# SCH_Dashboy_camera_2023-03-13.net
KiCad netlist of a schematic drawn in EasyEDA
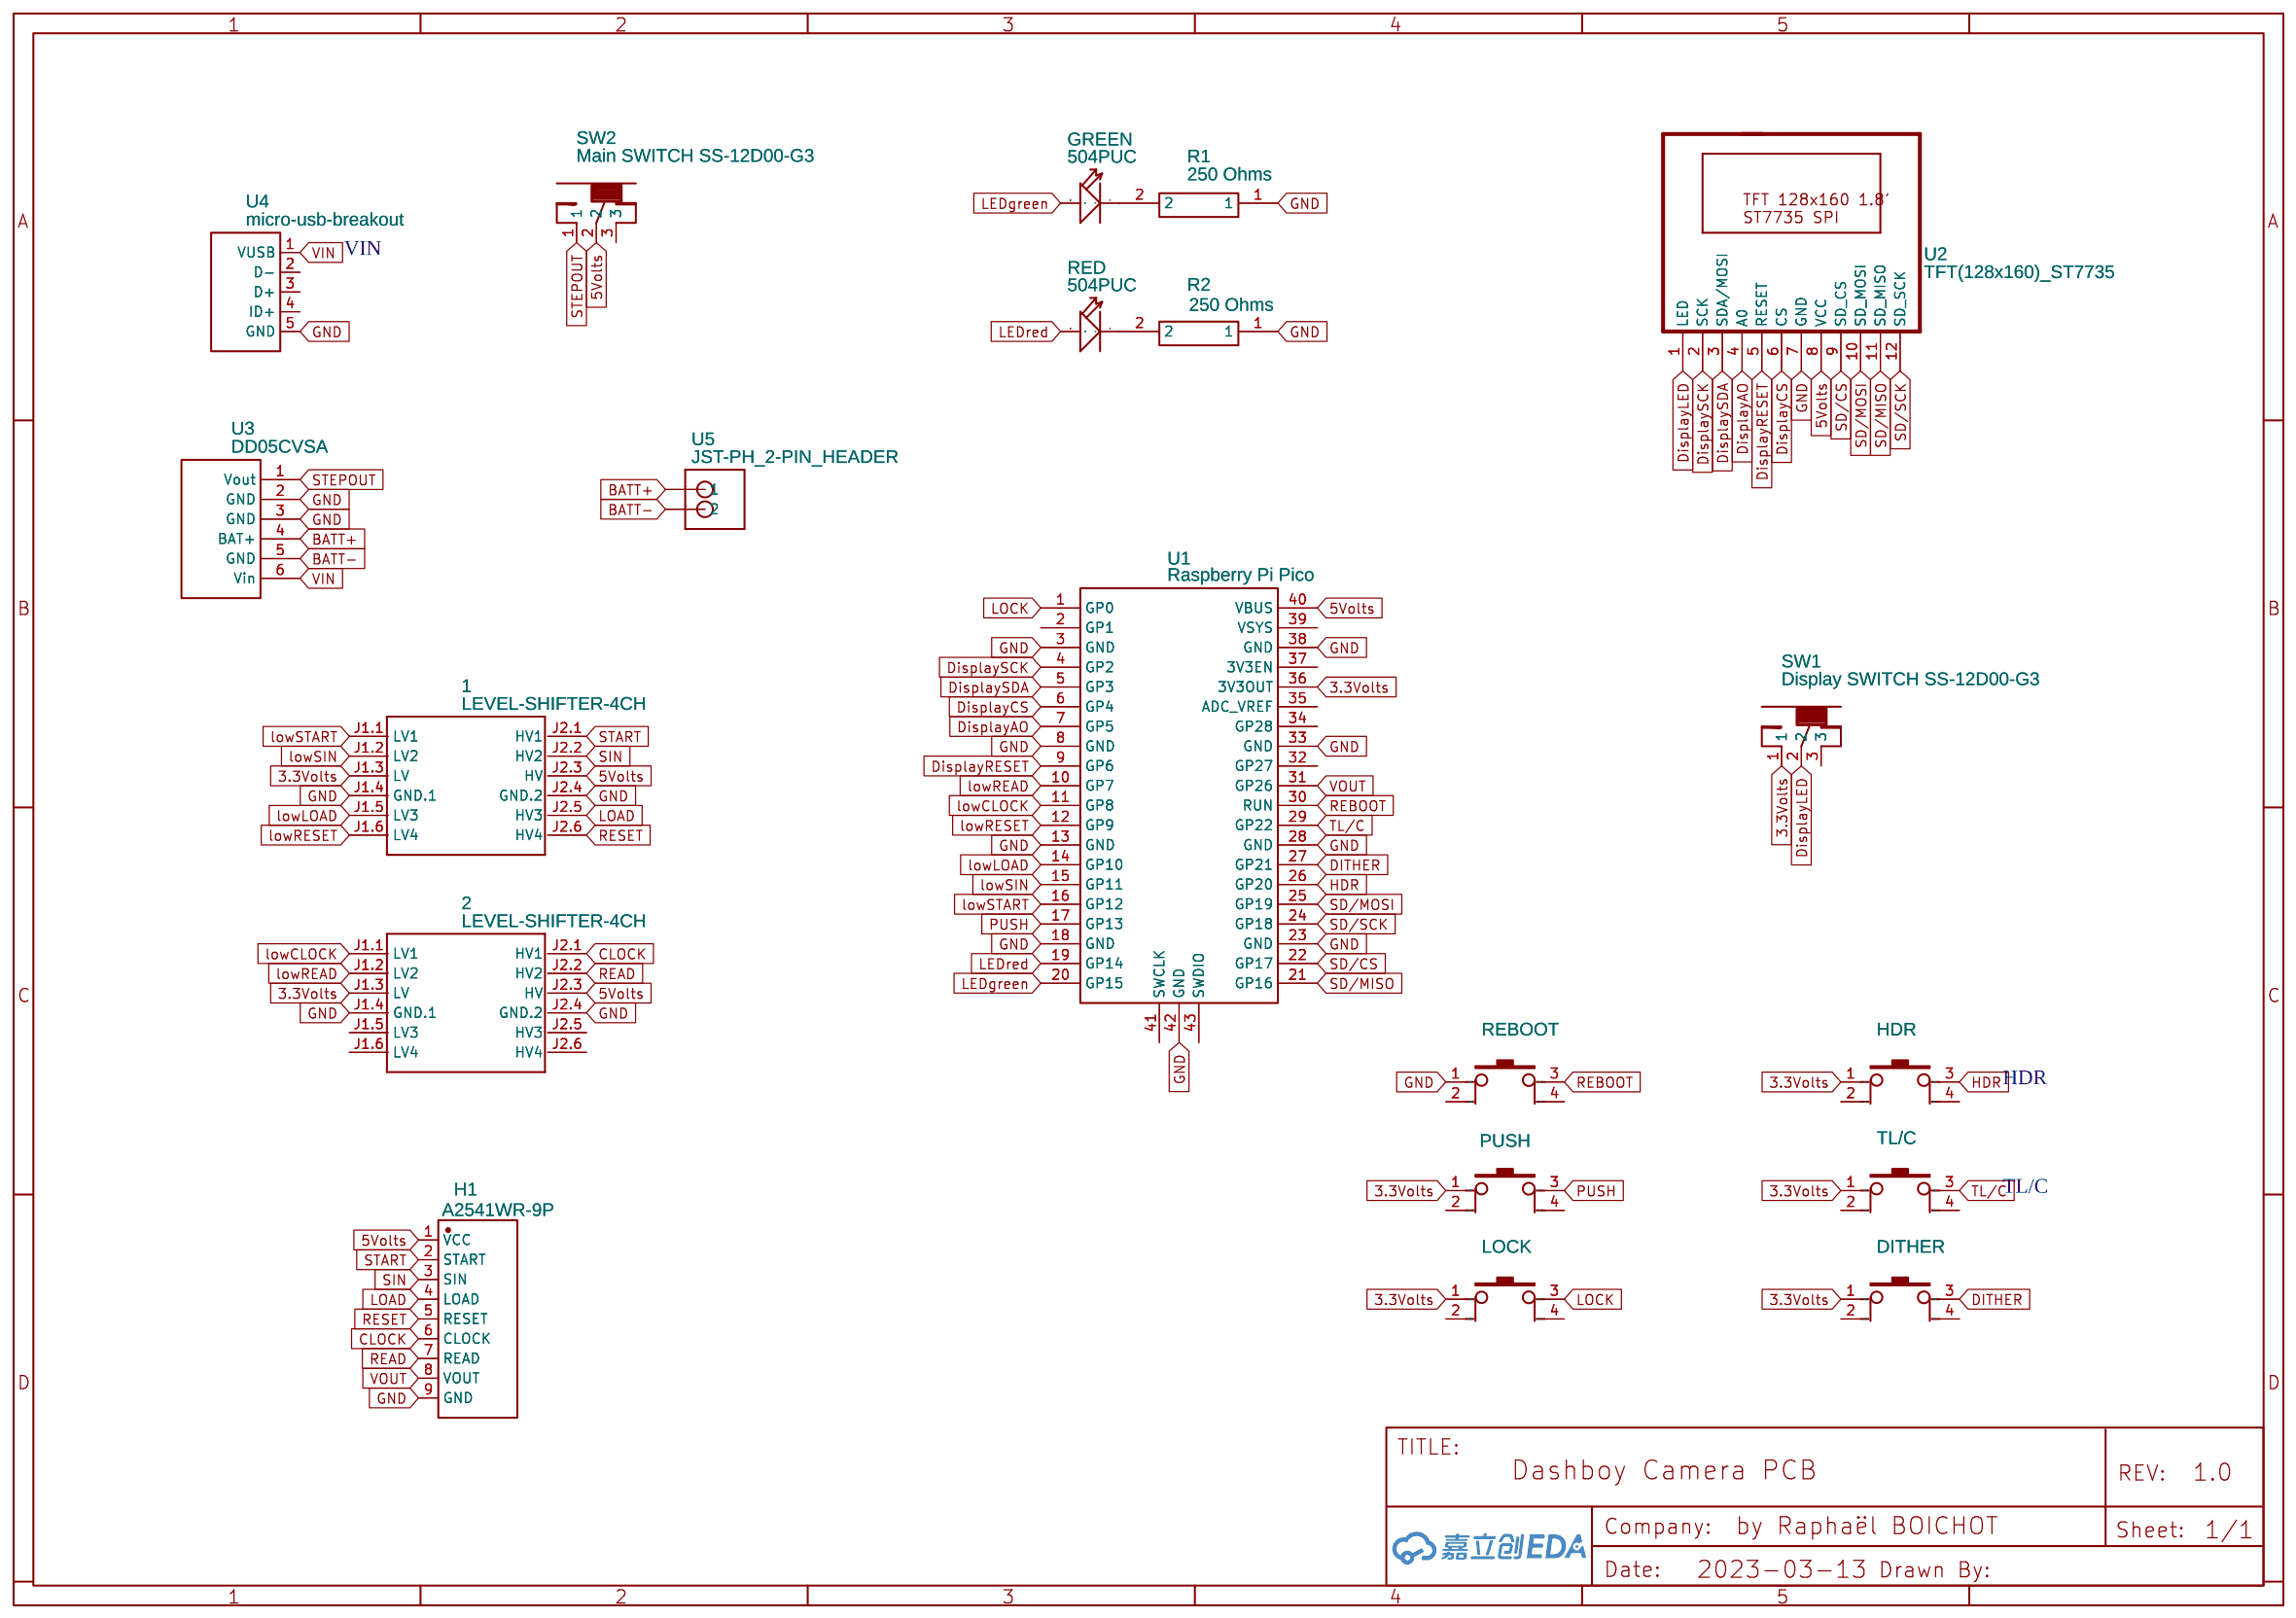
[diagram p0: schematic sheet]

(export (version "E")
  (design (tool "Eeschema 10.0.6"))
  (components
    (comp (ref "1") (value "LEVEL-SHIFTER-4CH") (libsource (lib "") (part "LEVEL-SHIFTER-4CH")))
    (comp (ref "2") (value "LEVEL-SHIFTER-4CH") (libsource (lib "") (part "LEVEL-SHIFTER-4CH")))
    (comp (ref "DITHER")
      (value "BoutonPoussoir")
      (fields
        (field (name "BOM_Manufacturer Part") "button6*6*8")
        (field (name "BOM_Supplier Part") "C59982")
      )
      (libsource (lib "") (part "BoutonPoussoir_1"))
    )
    (comp (ref "GREEN") (value "504PUC") (libsource (lib "") (part "504PUC_1")))
    (comp (ref "H1")
      (value "A2541WR-9P")
      (fields (field (name "BOM_Supplier Part") "C225495"))
      (libsource (lib "") (part "A2541WR-9P"))
    )
    (comp (ref "HDR")
      (value "BoutonPoussoir")
      (fields
        (field (name "BOM_Manufacturer Part") "button6*6*8")
        (field (name "BOM_Supplier Part") "C59982")
      )
      (libsource (lib "") (part "BoutonPoussoir_2"))
    )
    (comp (ref "LOCK")
      (value "BoutonPoussoir")
      (fields
        (field (name "BOM_Manufacturer Part") "button6*6*8")
        (field (name "BOM_Supplier Part") "C59982")
      )
      (libsource (lib "") (part "BoutonPoussoir"))
    )
    (comp (ref "PUSH")
      (value "BoutonPoussoir")
      (fields
        (field (name "BOM_Manufacturer Part") "button6*6*8")
        (field (name "BOM_Supplier Part") "C59982")
      )
      (libsource (lib "") (part "BoutonPoussoir_3"))
    )
    (comp (ref "R1") (value "250 Ohms") (libsource (lib "") (part "RESITOR")))
    (comp (ref "R2") (value "250 Ohms") (libsource (lib "") (part "RESITOR")))
    (comp (ref "REBOOT")
      (value "BoutonPoussoir")
      (fields
        (field (name "BOM_Manufacturer Part") "button6*6*8")
        (field (name "BOM_Supplier Part") "C59982")
      )
      (libsource (lib "") (part "BoutonPoussoir_4"))
    )
    (comp (ref "RED") (value "504PUC") (libsource (lib "") (part "504PUC")))
    (comp (ref "SW1")
      (value "Display SWITCH SS-12D00-G3")
      (fields (field (name "BOM_Manufacturer Part") "TOGGLE SWITCH SS-12D00-G3"))
      (libsource (lib "") (part "TOGGLE SWITCH SS-12D00-G3_1"))
    )
    (comp (ref "SW2")
      (value "Main SWITCH SS-12D00-G3")
      (fields (field (name "BOM_Manufacturer Part") "TOGGLE SWITCH SS-12D00-G3"))
      (libsource (lib "") (part "TOGGLE SWITCH SS-12D00-G3"))
    )
    (comp (ref "TL/C")
      (value "BoutonPoussoir")
      (fields
        (field (name "BOM_Manufacturer Part") "button6*6*8")
        (field (name "BOM_Supplier Part") "C59982")
      )
      (libsource (lib "") (part "BoutonPoussoir_5"))
    )
    (comp (ref "U1") (value "Raspberry Pi Pico") (libsource (lib "") (part "Raspberry Pi Pico")))
    (comp (ref "U2") (value "TFT(128x160)_ST7735") (libsource (lib "") (part "TFT(128x160)_ST7735")))
    (comp (ref "U3") (value "DD05CVSA") (libsource (lib "") (part "DD05CVSA")))
    (comp (ref "U4") (value "micro-usb-breakout") (libsource (lib "") (part "micro-usb-breakout")))
    (comp (ref "U5") (value "JST-PH_2-PIN_HEADER") (libsource (lib "") (part "JST-PH_2-PIN_HEADER")))
  )
  (nets
    (net (code "1") (name "3.3Volts") (class "Default")
      (node (ref "1") (pin "J1.3") (pinfunction "LV_J1.3") (pintype "bidirectional"))
      (node (ref "2") (pin "J1.3") (pinfunction "LV_J1.3") (pintype "bidirectional"))
      (node (ref "DITHER") (pin "1") (pinfunction "1_1") (pintype "input"))
      (node (ref "HDR") (pin "1") (pinfunction "1_1") (pintype "input"))
      (node (ref "LOCK") (pin "1") (pinfunction "1_1") (pintype "input"))
      (node (ref "PUSH") (pin "1") (pinfunction "1_1") (pintype "input"))
      (node (ref "SW1") (pin "1") (pinfunction "1_1") (pintype "bidirectional"))
      (node (ref "TL/C") (pin "1") (pinfunction "1_1") (pintype "input"))
      (node (ref "U1") (pin "36") (pinfunction "3V3OUT_36") (pintype "unspecified"))
    )
    (net (code "2") (name "5Volts") (class "Default")
      (node (ref "1") (pin "J2.3") (pinfunction "HV_J2.3") (pintype "bidirectional"))
      (node (ref "2") (pin "J2.3") (pinfunction "HV_J2.3") (pintype "bidirectional"))
      (node (ref "H1") (pin "1") (pinfunction "VCC_1") (pintype "unspecified"))
      (node (ref "SW2") (pin "2") (pinfunction "2_2") (pintype "bidirectional"))
      (node (ref "U1") (pin "40") (pinfunction "VBUS_40") (pintype "unspecified"))
      (node (ref "U2") (pin "8") (pinfunction "VCC_8") (pintype "input"))
    )
    (net (code "3") (name "BATT+") (class "Default")
      (node (ref "U3") (pin "4") (pinfunction "BAT+_4") (pintype "unspecified"))
      (node (ref "U5") (pin "P1") (pinfunction "1_P1") (pintype "unspecified"))
    )
    (net (code "4") (name "BATT-") (class "Default")
      (node (ref "U3") (pin "5") (pinfunction "GND_5") (pintype "unspecified"))
      (node (ref "U5") (pin "P2") (pinfunction "2_P2") (pintype "unspecified"))
    )
    (net (code "5") (name "CLOCK") (class "Default")
      (node (ref "2") (pin "J2.1") (pinfunction "HV1_J2.1") (pintype "bidirectional"))
      (node (ref "H1") (pin "6") (pinfunction "CLOCK_6") (pintype "unspecified"))
    )
    (net (code "6") (name "DITHER") (class "Default")
      (node (ref "DITHER") (pin "3") (pinfunction "3_3") (pintype "input"))
      (node (ref "U1") (pin "27") (pinfunction "GP21_27") (pintype "unspecified"))
    )
    (net (code "7") (name "DisplayAO") (class "Default")
      (node (ref "U1") (pin "7") (pinfunction "GP5_7") (pintype "unspecified"))
      (node (ref "U2") (pin "4") (pinfunction "A0_4") (pintype "input"))
    )
    (net (code "8") (name "DisplayCS") (class "Default")
      (node (ref "U1") (pin "6") (pinfunction "GP4_6") (pintype "unspecified"))
      (node (ref "U2") (pin "6") (pinfunction "CS_6") (pintype "input"))
    )
    (net (code "9") (name "DisplayLED") (class "Default")
      (node (ref "SW1") (pin "2") (pinfunction "2_2") (pintype "bidirectional"))
      (node (ref "U2") (pin "1") (pinfunction "LED_1") (pintype "passive"))
    )
    (net (code "10") (name "DisplayRESET") (class "Default")
      (node (ref "U1") (pin "9") (pinfunction "GP6_9") (pintype "unspecified"))
      (node (ref "U2") (pin "5") (pinfunction "RESET_5") (pintype "input"))
    )
    (net (code "11") (name "DisplaySCK") (class "Default")
      (node (ref "U1") (pin "4") (pinfunction "GP2_4") (pintype "unspecified"))
      (node (ref "U2") (pin "2") (pinfunction "SCK_2") (pintype "output"))
    )
    (net (code "12") (name "DisplaySDA") (class "Default")
      (node (ref "U1") (pin "5") (pinfunction "GP3_5") (pintype "unspecified"))
      (node (ref "U2") (pin "3") (pinfunction "SDA/MOSI_3") (pintype "input"))
    )
    (net (code "13") (name "GND") (class "Default")
      (node (ref "1") (pin "J1.4") (pinfunction "GND.1_J1.4") (pintype "bidirectional"))
      (node (ref "1") (pin "J2.4") (pinfunction "GND.2_J2.4") (pintype "bidirectional"))
      (node (ref "2") (pin "J1.4") (pinfunction "GND.1_J1.4") (pintype "bidirectional"))
      (node (ref "2") (pin "J2.4") (pinfunction "GND.2_J2.4") (pintype "bidirectional"))
      (node (ref "H1") (pin "9") (pinfunction "GND_9") (pintype "unspecified"))
      (node (ref "R1") (pin "1") (pinfunction "1_1") (pintype "unspecified"))
      (node (ref "R2") (pin "1") (pinfunction "1_1") (pintype "unspecified"))
      (node (ref "REBOOT") (pin "1") (pinfunction "1_1") (pintype "input"))
      (node (ref "U1") (pin "13") (pinfunction "GND_13") (pintype "unspecified"))
      (node (ref "U1") (pin "18") (pinfunction "GND_18") (pintype "unspecified"))
      (node (ref "U1") (pin "23") (pinfunction "GND_23") (pintype "unspecified"))
      (node (ref "U1") (pin "28") (pinfunction "GND_28") (pintype "unspecified"))
      (node (ref "U1") (pin "3") (pinfunction "GND_3") (pintype "unspecified"))
      (node (ref "U1") (pin "33") (pinfunction "GND_33") (pintype "unspecified"))
      (node (ref "U1") (pin "38") (pinfunction "GND_38") (pintype "unspecified"))
      (node (ref "U1") (pin "42") (pinfunction "GND_42") (pintype "unspecified"))
      (node (ref "U1") (pin "8") (pinfunction "GND_8") (pintype "unspecified"))
      (node (ref "U2") (pin "7") (pinfunction "GND_7") (pintype "unspecified"))
      (node (ref "U3") (pin "2") (pinfunction "GND_2") (pintype "unspecified"))
      (node (ref "U3") (pin "3") (pinfunction "GND_3") (pintype "unspecified"))
      (node (ref "U4") (pin "5") (pinfunction "GND_5") (pintype "unspecified"))
    )
    (net (code "14") (name "HDR") (class "Default")
      (node (ref "HDR") (pin "3") (pinfunction "3_3") (pintype "input"))
      (node (ref "U1") (pin "26") (pinfunction "GP20_26") (pintype "unspecified"))
    )
    (net (code "15") (name "LEDgreen") (class "Default")
      (node (ref "GREEN") (pin "+") (pinfunction "+_+") (pintype "unspecified"))
      (node (ref "U1") (pin "20") (pinfunction "GP15_20") (pintype "unspecified"))
    )
    (net (code "16") (name "LEDred") (class "Default")
      (node (ref "RED") (pin "+") (pinfunction "+_+") (pintype "unspecified"))
      (node (ref "U1") (pin "19") (pinfunction "GP14_19") (pintype "unspecified"))
    )
    (net (code "17") (name "LOAD") (class "Default")
      (node (ref "1") (pin "J2.5") (pinfunction "HV3_J2.5") (pintype "bidirectional"))
      (node (ref "H1") (pin "4") (pinfunction "LOAD_4") (pintype "unspecified"))
    )
    (net (code "18") (name "LOCK") (class "Default")
      (node (ref "LOCK") (pin "3") (pinfunction "3_3") (pintype "input"))
      (node (ref "U1") (pin "1") (pinfunction "GP0_1") (pintype "unspecified"))
    )
    (net (code "19") (name "Net-(GREEN-Pad-)") (class "Default")
      (node (ref "GREEN") (pin "-") (pinfunction "-_-") (pintype "unspecified"))
      (node (ref "R1") (pin "2") (pinfunction "2_2") (pintype "unspecified"))
    )
    (net (code "20") (name "Net-(R2-Pad2)") (class "Default")
      (node (ref "R2") (pin "2") (pinfunction "2_2") (pintype "unspecified"))
      (node (ref "RED") (pin "-") (pinfunction "-_-") (pintype "unspecified"))
    )
    (net (code "21") (name "PUSH") (class "Default")
      (node (ref "PUSH") (pin "3") (pinfunction "3_3") (pintype "input"))
      (node (ref "U1") (pin "17") (pinfunction "GP13_17") (pintype "unspecified"))
    )
    (net (code "22") (name "READ") (class "Default")
      (node (ref "2") (pin "J2.2") (pinfunction "HV2_J2.2") (pintype "bidirectional"))
      (node (ref "H1") (pin "7") (pinfunction "READ_7") (pintype "unspecified"))
    )
    (net (code "23") (name "REBOOT") (class "Default")
      (node (ref "REBOOT") (pin "3") (pinfunction "3_3") (pintype "input"))
      (node (ref "U1") (pin "30") (pinfunction "RUN_30") (pintype "unspecified"))
    )
    (net (code "24") (name "RESET") (class "Default")
      (node (ref "1") (pin "J2.6") (pinfunction "HV4_J2.6") (pintype "bidirectional"))
      (node (ref "H1") (pin "5") (pinfunction "RESET_5") (pintype "unspecified"))
    )
    (net (code "25") (name "SD{slash}CS") (class "Default")
      (node (ref "U1") (pin "22") (pinfunction "GP17_22") (pintype "unspecified"))
      (node (ref "U2") (pin "9") (pinfunction "SD_CS_9") (pintype "input"))
    )
    (net (code "26") (name "SD{slash}MISO") (class "Default")
      (node (ref "U1") (pin "21") (pinfunction "GP16_21") (pintype "unspecified"))
      (node (ref "U2") (pin "11") (pinfunction "SD_MISO_11") (pintype "input"))
    )
    (net (code "27") (name "SD{slash}MOSI") (class "Default")
      (node (ref "U1") (pin "25") (pinfunction "GP19_25") (pintype "unspecified"))
      (node (ref "U2") (pin "10") (pinfunction "SD_MOSI_10") (pintype "input"))
    )
    (net (code "28") (name "SD{slash}SCK") (class "Default")
      (node (ref "U1") (pin "24") (pinfunction "GP18_24") (pintype "unspecified"))
      (node (ref "U2") (pin "12") (pinfunction "SD_SCK_12") (pintype "input"))
    )
    (net (code "29") (name "SIN") (class "Default")
      (node (ref "1") (pin "J2.2") (pinfunction "HV2_J2.2") (pintype "bidirectional"))
      (node (ref "H1") (pin "3") (pinfunction "SIN_3") (pintype "unspecified"))
    )
    (net (code "30") (name "START") (class "Default")
      (node (ref "1") (pin "J2.1") (pinfunction "HV1_J2.1") (pintype "bidirectional"))
      (node (ref "H1") (pin "2") (pinfunction "START_2") (pintype "unspecified"))
    )
    (net (code "31") (name "STEPOUT") (class "Default")
      (node (ref "SW2") (pin "1") (pinfunction "1_1") (pintype "bidirectional"))
      (node (ref "U3") (pin "1") (pinfunction "Vout_1") (pintype "unspecified"))
    )
    (net (code "32") (name "TL{slash}C") (class "Default")
      (node (ref "TL/C") (pin "3") (pinfunction "3_3") (pintype "input"))
      (node (ref "U1") (pin "29") (pinfunction "GP22_29") (pintype "unspecified"))
    )
    (net (code "33") (name "VIN") (class "Default")
      (node (ref "U3") (pin "6") (pinfunction "Vin_6") (pintype "unspecified"))
      (node (ref "U4") (pin "1") (pinfunction "VUSB_1") (pintype "unspecified"))
    )
    (net (code "34") (name "VOUT") (class "Default")
      (node (ref "H1") (pin "8") (pinfunction "VOUT_8") (pintype "unspecified"))
      (node (ref "U1") (pin "31") (pinfunction "GP26_31") (pintype "unspecified"))
    )
    (net (code "35") (name "lowCLOCK") (class "Default")
      (node (ref "2") (pin "J1.1") (pinfunction "LV1_J1.1") (pintype "bidirectional"))
      (node (ref "U1") (pin "11") (pinfunction "GP8_11") (pintype "unspecified"))
    )
    (net (code "36") (name "lowLOAD") (class "Default")
      (node (ref "1") (pin "J1.5") (pinfunction "LV3_J1.5") (pintype "bidirectional"))
      (node (ref "U1") (pin "14") (pinfunction "GP10_14") (pintype "unspecified"))
    )
    (net (code "37") (name "lowREAD") (class "Default")
      (node (ref "2") (pin "J1.2") (pinfunction "LV2_J1.2") (pintype "bidirectional"))
      (node (ref "U1") (pin "10") (pinfunction "GP7_10") (pintype "unspecified"))
    )
    (net (code "38") (name "lowRESET") (class "Default")
      (node (ref "1") (pin "J1.6") (pinfunction "LV4_J1.6") (pintype "bidirectional"))
      (node (ref "U1") (pin "12") (pinfunction "GP9_12") (pintype "unspecified"))
    )
    (net (code "39") (name "lowSIN") (class "Default")
      (node (ref "1") (pin "J1.2") (pinfunction "LV2_J1.2") (pintype "bidirectional"))
      (node (ref "U1") (pin "15") (pinfunction "GP11_15") (pintype "unspecified"))
    )
    (net (code "40") (name "lowSTART") (class "Default")
      (node (ref "1") (pin "J1.1") (pinfunction "LV1_J1.1") (pintype "bidirectional"))
      (node (ref "U1") (pin "16") (pinfunction "GP12_16") (pintype "unspecified"))
    )
    (net (code "41") (name "unconnected-(2-HV3-PadJ2.5)") (class "Default")
      (node (ref "2") (pin "J2.5") (pinfunction "HV3_J2.5") (pintype "bidirectional"))
    )
    (net (code "42") (name "unconnected-(2-HV4-PadJ2.6)") (class "Default")
      (node (ref "2") (pin "J2.6") (pinfunction "HV4_J2.6") (pintype "bidirectional"))
    )
    (net (code "43") (name "unconnected-(2-LV3-PadJ1.5)") (class "Default")
      (node (ref "2") (pin "J1.5") (pinfunction "LV3_J1.5") (pintype "bidirectional"))
    )
    (net (code "44") (name "unconnected-(2-LV4-PadJ1.6)") (class "Default")
      (node (ref "2") (pin "J1.6") (pinfunction "LV4_J1.6") (pintype "bidirectional"))
    )
    (net (code "45") (name "unconnected-(DITHER-Pad2)") (class "Default")
      (node (ref "DITHER") (pin "2") (pinfunction "2_2") (pintype "input"))
    )
    (net (code "46") (name "unconnected-(DITHER-Pad4)") (class "Default")
      (node (ref "DITHER") (pin "4") (pinfunction "4_4") (pintype "input"))
    )
    (net (code "47") (name "unconnected-(HDR-Pad2)") (class "Default")
      (node (ref "HDR") (pin "2") (pinfunction "2_2") (pintype "input"))
    )
    (net (code "48") (name "unconnected-(HDR-Pad4)") (class "Default")
      (node (ref "HDR") (pin "4") (pinfunction "4_4") (pintype "input"))
    )
    (net (code "49") (name "unconnected-(LOCK-Pad2)") (class "Default")
      (node (ref "LOCK") (pin "2") (pinfunction "2_2") (pintype "input"))
    )
    (net (code "50") (name "unconnected-(LOCK-Pad4)") (class "Default")
      (node (ref "LOCK") (pin "4") (pinfunction "4_4") (pintype "input"))
    )
    (net (code "51") (name "unconnected-(PUSH-Pad2)") (class "Default")
      (node (ref "PUSH") (pin "2") (pinfunction "2_2") (pintype "input"))
    )
    (net (code "52") (name "unconnected-(PUSH-Pad4)") (class "Default")
      (node (ref "PUSH") (pin "4") (pinfunction "4_4") (pintype "input"))
    )
    (net (code "53") (name "unconnected-(REBOOT-Pad2)") (class "Default")
      (node (ref "REBOOT") (pin "2") (pinfunction "2_2") (pintype "input"))
    )
    (net (code "54") (name "unconnected-(REBOOT-Pad4)") (class "Default")
      (node (ref "REBOOT") (pin "4") (pinfunction "4_4") (pintype "input"))
    )
    (net (code "55") (name "unconnected-(SW1-Pad3)") (class "Default")
      (node (ref "SW1") (pin "3") (pinfunction "3_3") (pintype "unspecified"))
    )
    (net (code "56") (name "unconnected-(SW2-Pad3)") (class "Default")
      (node (ref "SW2") (pin "3") (pinfunction "3_3") (pintype "unspecified"))
    )
    (net (code "57") (name "unconnected-(TL/C-Pad2)") (class "Default")
      (node (ref "TL/C") (pin "2") (pinfunction "2_2") (pintype "input"))
    )
    (net (code "58") (name "unconnected-(TL/C-Pad4)") (class "Default")
      (node (ref "TL/C") (pin "4") (pinfunction "4_4") (pintype "input"))
    )
    (net (code "59") (name "unconnected-(U1-3V3EN-Pad37)") (class "Default")
      (node (ref "U1") (pin "37") (pinfunction "3V3EN_37") (pintype "unspecified"))
    )
    (net (code "60") (name "unconnected-(U1-ADC_VREF-Pad35)") (class "Default")
      (node (ref "U1") (pin "35") (pinfunction "ADC_VREF_35") (pintype "unspecified"))
    )
    (net (code "61") (name "unconnected-(U1-GP1-Pad2)") (class "Default")
      (node (ref "U1") (pin "2") (pinfunction "GP1_2") (pintype "unspecified"))
    )
    (net (code "62") (name "unconnected-(U1-GP27-Pad32)") (class "Default")
      (node (ref "U1") (pin "32") (pinfunction "GP27_32") (pintype "unspecified"))
    )
    (net (code "63") (name "unconnected-(U1-GP28-Pad34)") (class "Default")
      (node (ref "U1") (pin "34") (pinfunction "GP28_34") (pintype "unspecified"))
    )
    (net (code "64") (name "unconnected-(U1-SWCLK-Pad41)") (class "Default")
      (node (ref "U1") (pin "41") (pinfunction "SWCLK_41") (pintype "unspecified"))
    )
    (net (code "65") (name "unconnected-(U1-SWDIO-Pad43)") (class "Default")
      (node (ref "U1") (pin "43") (pinfunction "SWDIO_43") (pintype "unspecified"))
    )
    (net (code "66") (name "unconnected-(U1-VSYS-Pad39)") (class "Default")
      (node (ref "U1") (pin "39") (pinfunction "VSYS_39") (pintype "unspecified"))
    )
    (net (code "67") (name "unconnected-(U4-D+-Pad3)") (class "Default")
      (node (ref "U4") (pin "3") (pinfunction "D+_3") (pintype "unspecified"))
    )
    (net (code "68") (name "unconnected-(U4-D--Pad2)") (class "Default")
      (node (ref "U4") (pin "2") (pinfunction "D-_2") (pintype "unspecified"))
    )
    (net (code "69") (name "unconnected-(U4-ID+-Pad4)") (class "Default")
      (node (ref "U4") (pin "4") (pinfunction "ID+_4") (pintype "unspecified"))
    )
  )
)
